# 3_Digital.net
KiCad netlist of a schematic drawn in Altium Designer
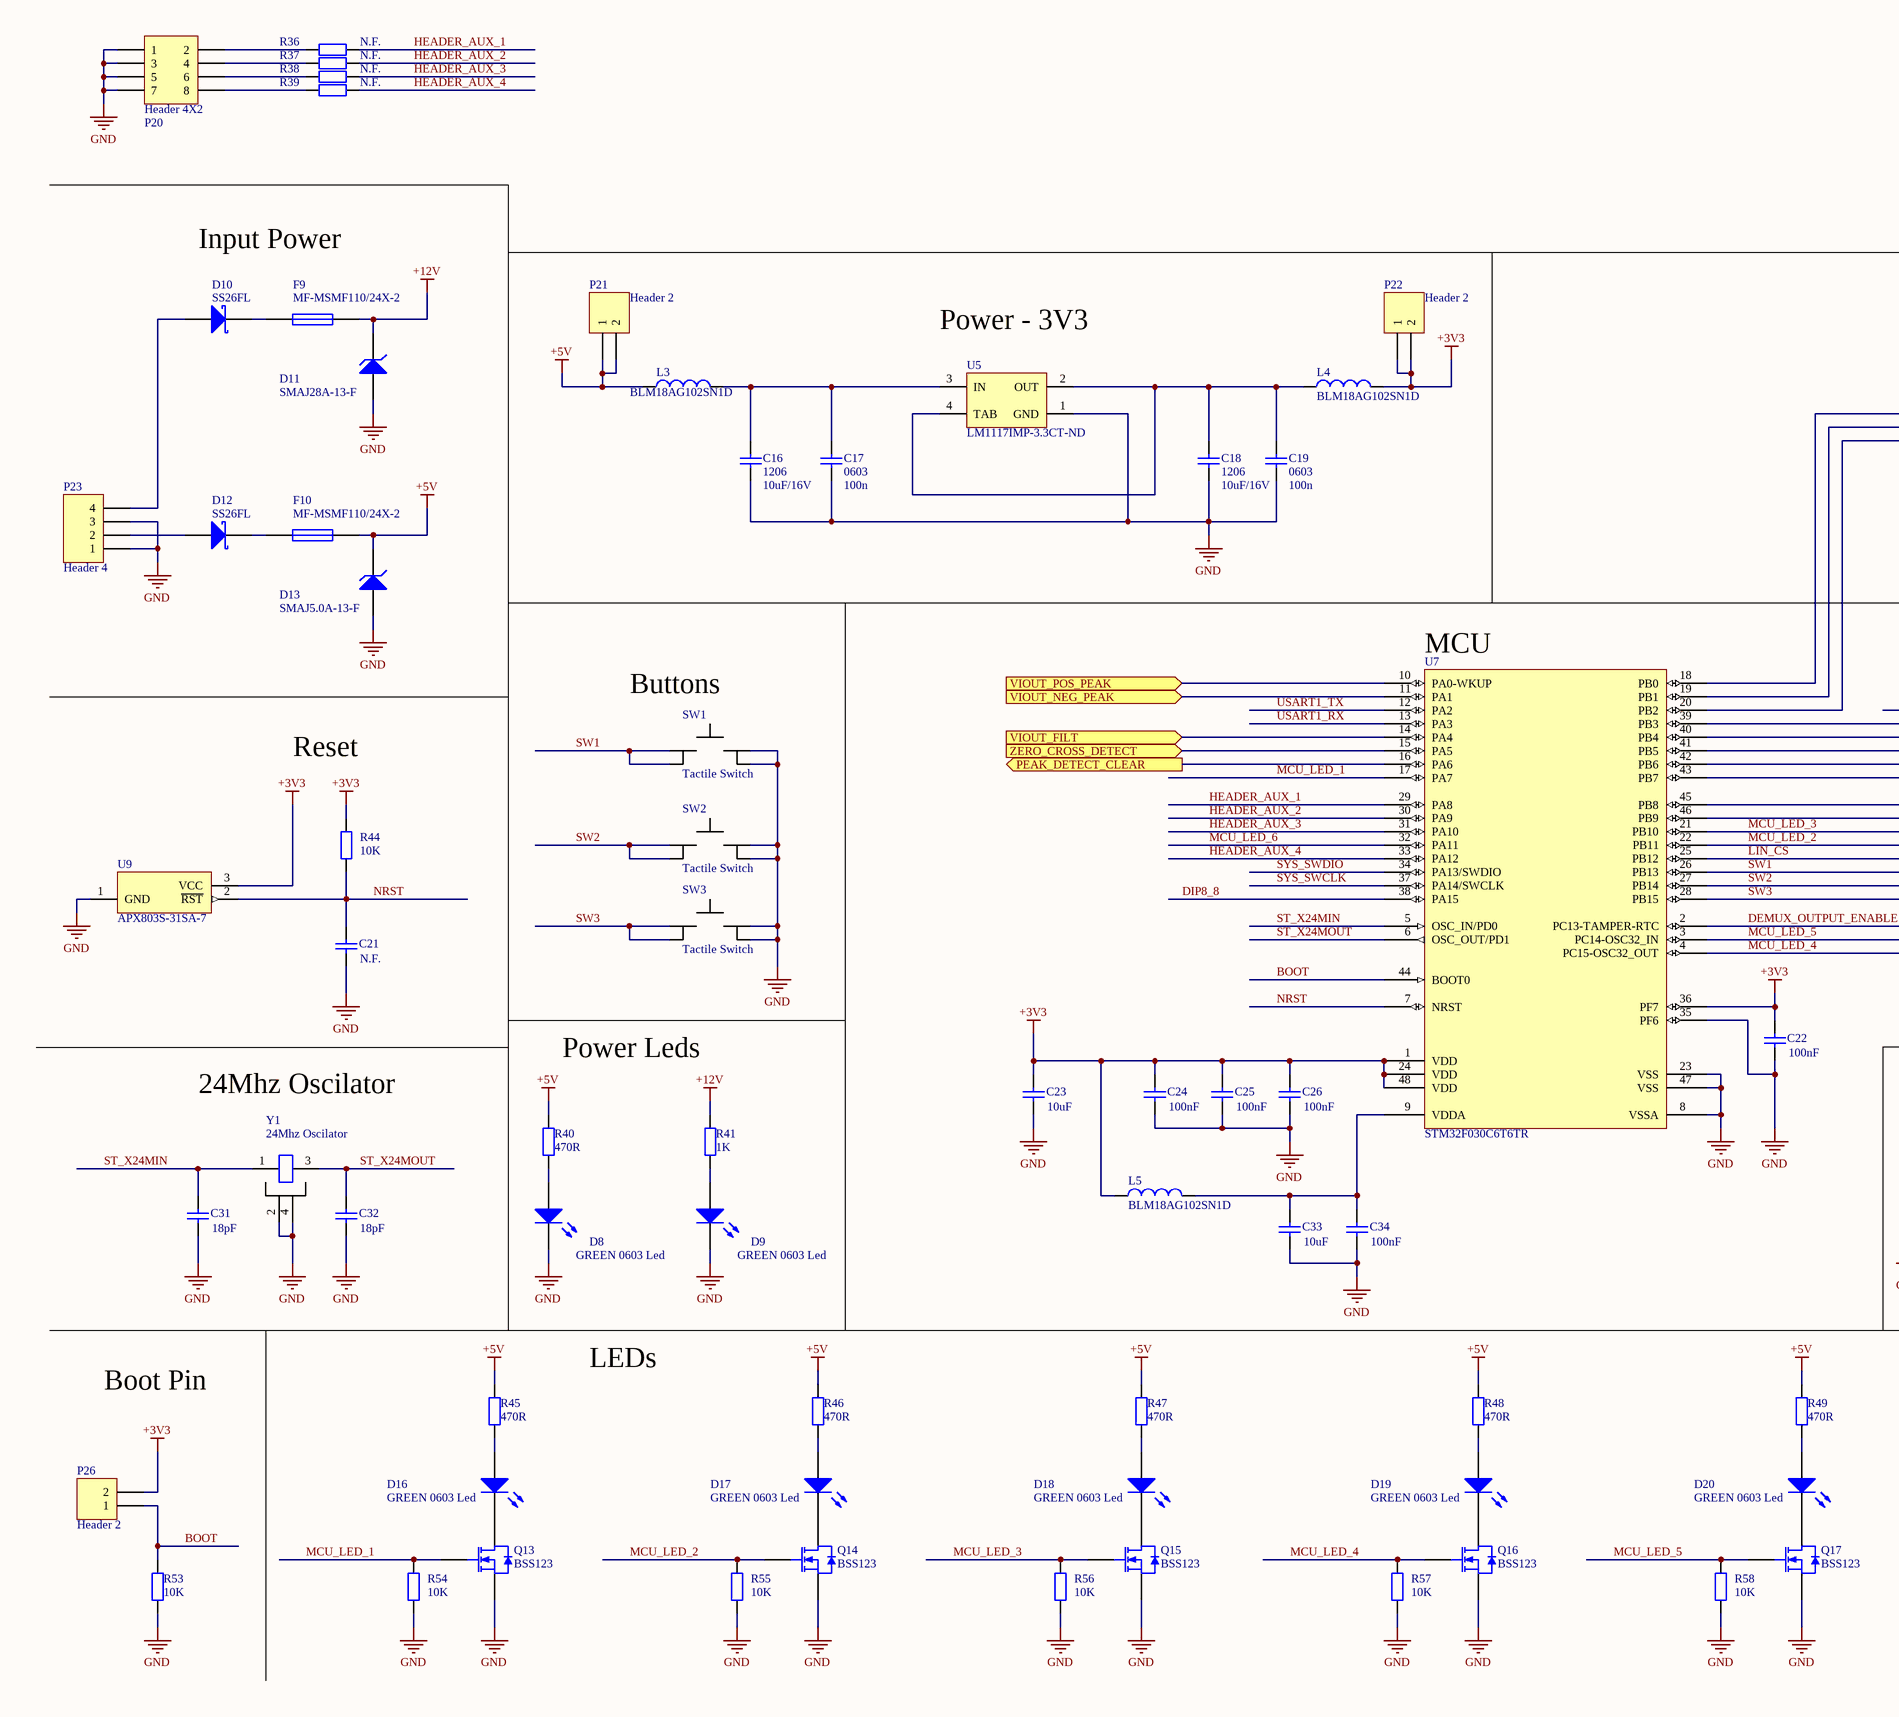
[diagram p0: [3]Digital.SchDoc, left]
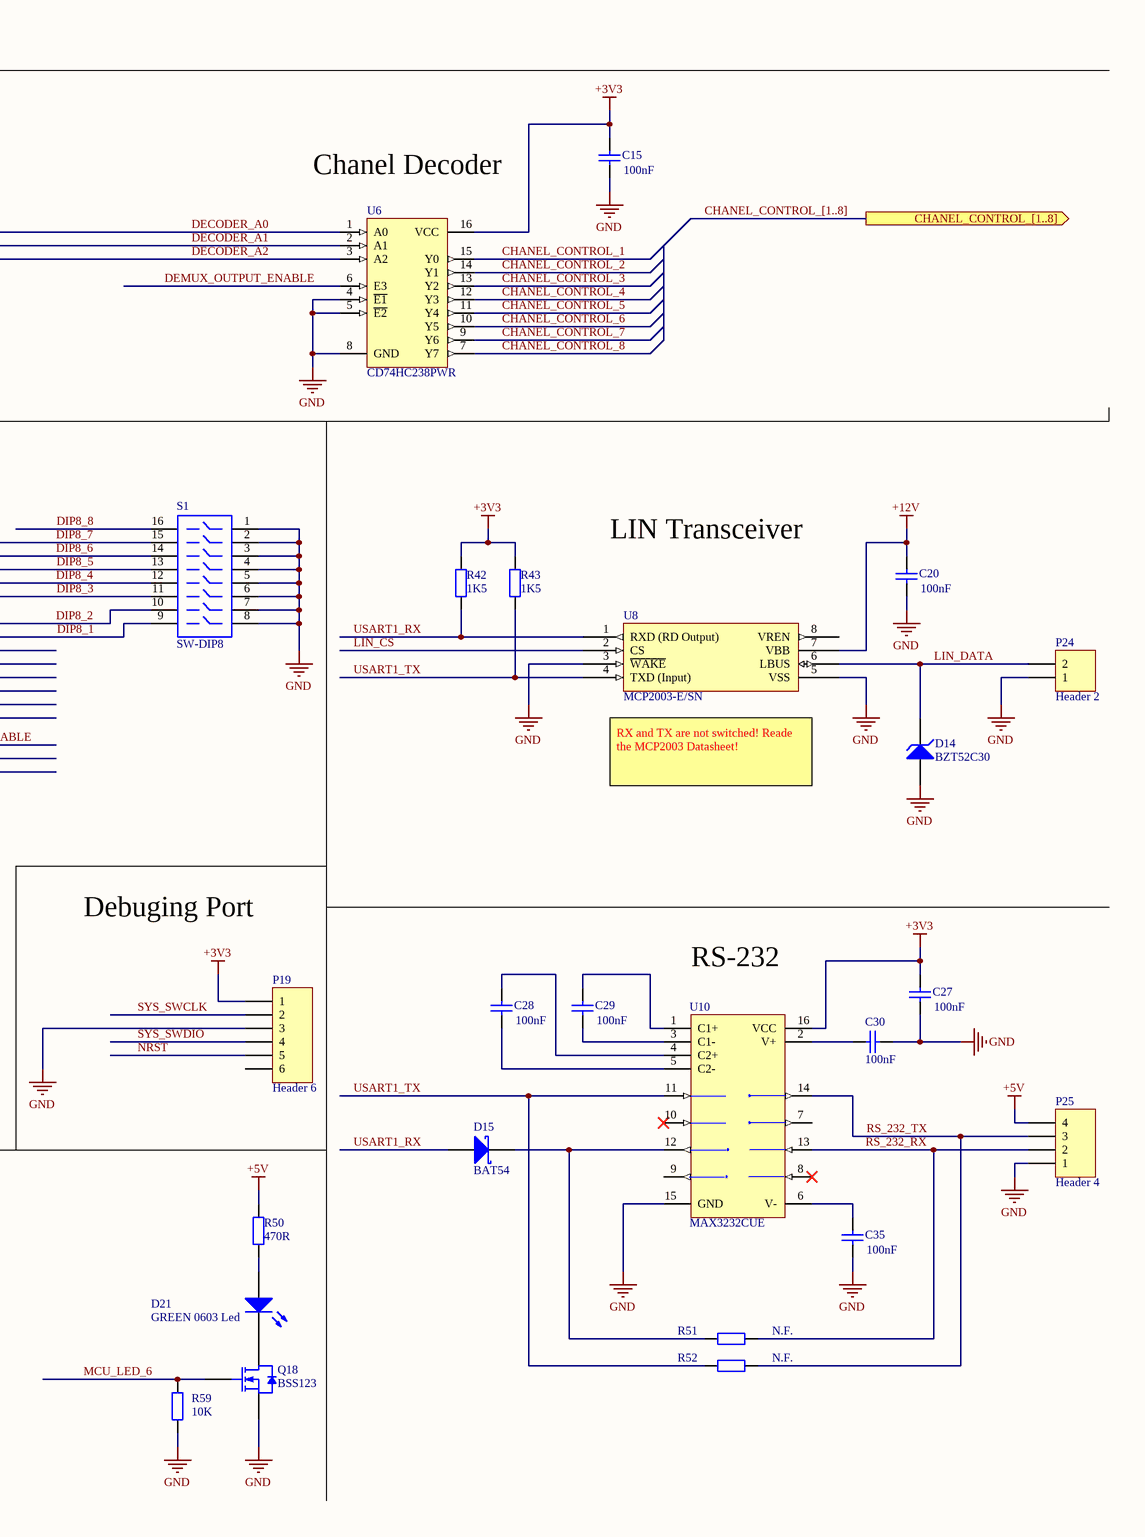
[diagram p1: [3]Digital.SchDoc, right]

(export (version "E")
  (design (tool "Eeschema 10.0.6"))
  (components
    (comp (ref "C15")
      (value "100nF")
      (footprint "1608[0603]")
      (description "Capacitor")
      (fields (field (name "Comment") "0603") (field (name "PUBLISHER") "Altium Limited"))
      (libsource (lib "Miscellaneous Devices") (part "Cap"))
    )
    (comp (ref "C16")
      (value "1206")
      (footprint "C1206")
      (description "Capacitor")
      (fields (field (name "ALTIUM_VALUE") "10uF/16V") (field (name "PUBLISHER") "Altium Limited"))
      (libsource (lib "Miscellaneous Devices") (part "Cap"))
    )
    (comp (ref "C17")
      (value "0603")
      (footprint "1608[0603]")
      (description "Capacitor")
      (fields (field (name "ALTIUM_VALUE") "100n") (field (name "PUBLISHER") "Altium Limited"))
      (libsource (lib "Miscellaneous Devices") (part "Cap"))
    )
    (comp (ref "C18")
      (value "1206")
      (footprint "C1206")
      (description "Capacitor")
      (fields (field (name "ALTIUM_VALUE") "10uF/16V") (field (name "PUBLISHER") "Altium Limited"))
      (libsource (lib "Miscellaneous Devices") (part "Cap"))
    )
    (comp (ref "C19")
      (value "0603")
      (footprint "1608[0603]")
      (description "Capacitor")
      (fields (field (name "ALTIUM_VALUE") "100n") (field (name "PUBLISHER") "Altium Limited"))
      (libsource (lib "Miscellaneous Devices") (part "Cap"))
    )
    (comp (ref "C20")
      (value "100nF")
      (footprint "1608[0603]")
      (description "Capacitor")
      (fields (field (name "Comment") "0603") (field (name "PUBLISHER") "Altium Limited"))
      (libsource (lib "Miscellaneous Devices") (part "Cap"))
    )
    (comp (ref "C21")
      (value "N.F.")
      (footprint "1608[0603]")
      (description "Capacitor")
      (fields (field (name "Comment") "0603") (field (name "PUBLISHER") "Altium Limited"))
      (libsource (lib "Miscellaneous Devices") (part "Cap"))
    )
    (comp (ref "C22")
      (value "100nF")
      (footprint "1608[0603]")
      (description "Capacitor")
      (fields (field (name "Comment") "0603") (field (name "PUBLISHER") "Altium Limited"))
      (libsource (lib "Miscellaneous Devices") (part "Cap"))
    )
    (comp (ref "C23")
      (value "10uF")
      (footprint "1608[0603]")
      (description "Capacitor")
      (fields (field (name "Comment") "0603") (field (name "PUBLISHER") "Altium Limited"))
      (libsource (lib "Miscellaneous Devices") (part "Cap"))
    )
    (comp (ref "C24")
      (value "100nF")
      (footprint "1608[0603]")
      (description "Capacitor")
      (fields (field (name "Comment") "0603") (field (name "PUBLISHER") "Altium Limited"))
      (libsource (lib "Miscellaneous Devices") (part "Cap"))
    )
    (comp (ref "C25")
      (value "100nF")
      (footprint "1608[0603]")
      (description "Capacitor")
      (fields (field (name "Comment") "0603") (field (name "PUBLISHER") "Altium Limited"))
      (libsource (lib "Miscellaneous Devices") (part "Cap"))
    )
    (comp (ref "C26")
      (value "100nF")
      (footprint "1608[0603]")
      (description "Capacitor")
      (fields (field (name "Comment") "0603") (field (name "PUBLISHER") "Altium Limited"))
      (libsource (lib "Miscellaneous Devices") (part "Cap"))
    )
    (comp (ref "C27")
      (value "100nF")
      (footprint "1608[0603]")
      (description "Capacitor")
      (fields (field (name "Comment") "0603") (field (name "PUBLISHER") "Altium Limited"))
      (libsource (lib "Miscellaneous Devices") (part "Cap"))
    )
    (comp (ref "C28")
      (value "100nF")
      (footprint "1608[0603]")
      (description "Capacitor")
      (fields (field (name "Comment") "0603") (field (name "PUBLISHER") "Altium Limited"))
      (libsource (lib "Miscellaneous Devices") (part "Cap"))
    )
    (comp (ref "C29")
      (value "100nF")
      (footprint "1608[0603]")
      (description "Capacitor")
      (fields (field (name "Comment") "0603") (field (name "PUBLISHER") "Altium Limited"))
      (libsource (lib "Miscellaneous Devices") (part "Cap"))
    )
    (comp (ref "C30")
      (value "100nF")
      (footprint "1608[0603]")
      (description "Capacitor")
      (fields (field (name "Comment") "0603") (field (name "PUBLISHER") "Altium Limited"))
      (libsource (lib "Miscellaneous Devices") (part "Cap"))
    )
    (comp (ref "C31")
      (value "18pF")
      (footprint "1608[0603]")
      (description "Capacitor")
      (fields (field (name "Comment") "0603") (field (name "PUBLISHER") "Altium Limited"))
      (libsource (lib "Miscellaneous Devices") (part "Cap"))
    )
    (comp (ref "C32")
      (value "18pF")
      (footprint "1608[0603]")
      (description "Capacitor")
      (fields (field (name "Comment") "0603") (field (name "PUBLISHER") "Altium Limited"))
      (libsource (lib "Miscellaneous Devices") (part "Cap"))
    )
    (comp (ref "C33")
      (value "10uF")
      (footprint "1608[0603]")
      (description "Capacitor")
      (fields (field (name "Comment") "0603") (field (name "PUBLISHER") "Altium Limited"))
      (libsource (lib "Miscellaneous Devices") (part "Cap"))
    )
    (comp (ref "C34")
      (value "100nF")
      (footprint "1608[0603]")
      (description "Capacitor")
      (fields (field (name "Comment") "0603") (field (name "PUBLISHER") "Altium Limited"))
      (libsource (lib "Miscellaneous Devices") (part "Cap"))
    )
    (comp (ref "C35")
      (value "100nF")
      (footprint "1608[0603]")
      (description "Capacitor")
      (fields (field (name "Comment") "0603") (field (name "PUBLISHER") "Altium Limited"))
      (libsource (lib "Miscellaneous Devices") (part "Cap"))
    )
    (comp (ref "D8")
      (value "GREEN 0603 Led")
      (footprint "LED0603")
      (description "Typical INFRARED GaAs LED")
      (fields
        (field (name "MANUFACTURER PART NO.") "KPT-1608CGCK")
        (field (name "PUBLISHER") "Altium Limited")
      )
      (libsource (lib "Miscellaneous Devices") (part "LED0"))
    )
    (comp (ref "D9")
      (value "GREEN 0603 Led")
      (footprint "LED0603")
      (description "Typical INFRARED GaAs LED")
      (fields
        (field (name "MANUFACTURER PART NO.") "KPT-1608CGCK")
        (field (name "PUBLISHER") "Altium Limited")
      )
      (libsource (lib "Miscellaneous Devices") (part "LED0"))
    )
    (comp (ref "D10")
      (value "SS26FL")
      (footprint "SOD123F")
      (description "Schottky Rectifier")
      (fields (field (name "PUBLISHER") "Altium Limited"))
      (libsource (lib "Miscellaneous Devices") (part "Diode 11DQ03"))
    )
    (comp (ref "D11")
      (value "SMAJ28A-13-F")
      (footprint "SMA")
      (description "Zener Diode")
      (fields (field (name "PUBLISHER") "Altium Limited"))
      (libsource (lib "Miscellaneous Devices") (part "D Zener"))
    )
    (comp (ref "D12")
      (value "SS26FL")
      (footprint "SOD123F")
      (description "Schottky Rectifier")
      (fields (field (name "PUBLISHER") "Altium Limited"))
      (libsource (lib "Miscellaneous Devices") (part "Diode 11DQ03"))
    )
    (comp (ref "D13")
      (value "SMAJ5.0A-13-F")
      (footprint "SMA")
      (description "Zener Diode")
      (fields (field (name "PUBLISHER") "Altium Limited"))
      (libsource (lib "Miscellaneous Devices") (part "D Zener"))
    )
    (comp (ref "D14")
      (value "BZT52C30")
      (footprint "SOD123")
      (description "Zener Diode")
      (fields
        (field (name "MANUFACTURER PART NO.") "BZT52C30-7-F")
        (field (name "PUBLISHER") "Altium Limited")
      )
      (libsource (lib "Miscellaneous Devices") (part "D Zener"))
    )
    (comp (ref "D15")
      (value "BAT54")
      (footprint "SOT-23_N")
      (description "Silicon RF Schottky Diode for Mixer Applications in the VHF/UHF Range")
      (fields (field (name "MANUFACTURER PART NO.") "BAT54LT1G") (field (name "PUBLISHER") "Altium Limited"))
      (libsource (lib "Miscellaneous Devices") (part "Diode BAT17"))
    )
    (comp (ref "D16")
      (value "GREEN 0603 Led")
      (footprint "LED0603")
      (description "Typical INFRARED GaAs LED")
      (fields
        (field (name "MANUFACTURER PART NO.") "KPT-1608CGCK")
        (field (name "PUBLISHER") "Altium Limited")
      )
      (libsource (lib "Miscellaneous Devices") (part "LED0"))
    )
    (comp (ref "D17")
      (value "GREEN 0603 Led")
      (footprint "LED0603")
      (description "Typical INFRARED GaAs LED")
      (fields
        (field (name "MANUFACTURER PART NO.") "KPT-1608CGCK")
        (field (name "PUBLISHER") "Altium Limited")
      )
      (libsource (lib "Miscellaneous Devices") (part "LED0"))
    )
    (comp (ref "D18")
      (value "GREEN 0603 Led")
      (footprint "LED0603")
      (description "Typical INFRARED GaAs LED")
      (fields
        (field (name "MANUFACTURER PART NO.") "KPT-1608CGCK")
        (field (name "PUBLISHER") "Altium Limited")
      )
      (libsource (lib "Miscellaneous Devices") (part "LED0"))
    )
    (comp (ref "D19")
      (value "GREEN 0603 Led")
      (footprint "LED0603")
      (description "Typical INFRARED GaAs LED")
      (fields
        (field (name "MANUFACTURER PART NO.") "KPT-1608CGCK")
        (field (name "PUBLISHER") "Altium Limited")
      )
      (libsource (lib "Miscellaneous Devices") (part "LED0"))
    )
    (comp (ref "D20")
      (value "GREEN 0603 Led")
      (footprint "LED0603")
      (description "Typical INFRARED GaAs LED")
      (fields
        (field (name "MANUFACTURER PART NO.") "KPT-1608CGCK")
        (field (name "PUBLISHER") "Altium Limited")
      )
      (libsource (lib "Miscellaneous Devices") (part "LED0"))
    )
    (comp (ref "D21")
      (value "GREEN 0603 Led")
      (footprint "LED0603")
      (description "Typical INFRARED GaAs LED")
      (fields
        (field (name "MANUFACTURER PART NO.") "KPT-1608CGCK")
        (field (name "PUBLISHER") "Altium Limited")
      )
      (libsource (lib "Miscellaneous Devices") (part "LED0"))
    )
    (comp (ref "F9")
      (value "MF-MSMF110/24X-2")
      (footprint "CAPC4532L")
      (description "Fuse")
      (fields
        (field (name "MANUFACTURER PART NO.") "MF-MSMF050-2")
        (field (name "PUBLISHER") "Altium Limited")
      )
      (libsource (lib "Miscellaneous Devices") (part "Fuse 1"))
    )
    (comp (ref "F10")
      (value "MF-MSMF110/24X-2")
      (footprint "CAPC4532L")
      (description "Fuse")
      (fields
        (field (name "MANUFACTURER PART NO.") "MF-MSMF050-2")
        (field (name "PUBLISHER") "Altium Limited")
      )
      (libsource (lib "Miscellaneous Devices") (part "Fuse 1"))
    )
    (comp (ref "L3")
      (value "BLM18AG102SN1D")
      (footprint "1608[0603]")
      (description "Inductor")
      (libsource (lib "Miscellaneous Devices") (part "Inductor"))
    )
    (comp (ref "L4")
      (value "BLM18AG102SN1D")
      (footprint "1608[0603]")
      (description "Inductor")
      (libsource (lib "Miscellaneous Devices") (part "Inductor"))
    )
    (comp (ref "L5")
      (value "BLM18AG102SN1D")
      (footprint "1608[0603]")
      (description "Inductor")
      (libsource (lib "Miscellaneous Devices") (part "Inductor"))
    )
    (comp (ref "P19")
      (value "Header 6")
      (footprint "HDR1X6")
      (description "Header, 6-Pin")
      (fields (field (name "PUBLISHER") "Altium Limited"))
      (libsource (lib "Miscellaneous Connectors") (part "Header 6"))
    )
    (comp (ref "P20")
      (value "Header 4X2")
      (footprint "HDR2X4")
      (description "Header, 4-Pin, Dual row")
      (fields (field (name "PUBLISHER") "Altium Limited"))
      (libsource (lib "Miscellaneous Connectors") (part "Header 4X2"))
    )
    (comp (ref "P21")
      (value "Header 2")
      (footprint "HDR1X2")
      (description "Header, 2-Pin")
      (fields (field (name "PUBLISHER") "Altium Limited"))
      (libsource (lib "Miscellaneous Connectors") (part "Header 2"))
    )
    (comp (ref "P22")
      (value "Header 2")
      (footprint "HDR1X2")
      (description "Header, 2-Pin")
      (fields (field (name "PUBLISHER") "Altium Limited"))
      (libsource (lib "Miscellaneous Connectors") (part "Header 2"))
    )
    (comp (ref "P23")
      (value "Header 4")
      (footprint "284391-4")
      (description "Header, 4-Pin")
      (fields (field (name "PUBLISHER") "Altium Limited"))
      (libsource (lib "Miscellaneous Connectors") (part "Header 4"))
    )
    (comp (ref "P24")
      (value "Header 2")
      (footprint "284391-2")
      (description "Header, 2-Pin")
      (fields (field (name "PUBLISHER") "Altium Limited"))
      (libsource (lib "Miscellaneous Connectors") (part "Header 2"))
    )
    (comp (ref "P25")
      (value "Header 4")
      (footprint "284391-4")
      (description "Header, 4-Pin")
      (fields (field (name "PUBLISHER") "Altium Limited"))
      (libsource (lib "") (part "Header 4_1"))
    )
    (comp (ref "P26")
      (value "Header 2")
      (footprint "HDR1X2")
      (description "Header, 2-Pin")
      (fields (field (name "PUBLISHER") "Altium Limited"))
      (libsource (lib "") (part "Header 2_1"))
    )
    (comp (ref "Q13")
      (value "BSS123")
      (footprint "SOT23_N")
      (description "N-channel Enhancement Mode Vertical D-MOSFET")
      (fields (field (name "PUBLISHER") "Altium Limited"))
      (libsource (lib "Philips Discrete MOSFET - Low Power") (part "BSS123"))
    )
    (comp (ref "Q14")
      (value "BSS123")
      (footprint "SOT23_N")
      (description "N-channel Enhancement Mode Vertical D-MOSFET")
      (fields (field (name "PUBLISHER") "Altium Limited"))
      (libsource (lib "Philips Discrete MOSFET - Low Power") (part "BSS123"))
    )
    (comp (ref "Q15")
      (value "BSS123")
      (footprint "SOT23_N")
      (description "N-channel Enhancement Mode Vertical D-MOSFET")
      (fields (field (name "PUBLISHER") "Altium Limited"))
      (libsource (lib "Philips Discrete MOSFET - Low Power") (part "BSS123"))
    )
    (comp (ref "Q16")
      (value "BSS123")
      (footprint "SOT23_N")
      (description "N-channel Enhancement Mode Vertical D-MOSFET")
      (fields (field (name "PUBLISHER") "Altium Limited"))
      (libsource (lib "Philips Discrete MOSFET - Low Power") (part "BSS123"))
    )
    (comp (ref "Q17")
      (value "BSS123")
      (footprint "SOT23_N")
      (description "N-channel Enhancement Mode Vertical D-MOSFET")
      (fields (field (name "PUBLISHER") "Altium Limited"))
      (libsource (lib "Philips Discrete MOSFET - Low Power") (part "BSS123"))
    )
    (comp (ref "Q18")
      (value "BSS123")
      (footprint "SOT23_N")
      (description "N-channel Enhancement Mode Vertical D-MOSFET")
      (fields (field (name "PUBLISHER") "Altium Limited"))
      (libsource (lib "Philips Discrete MOSFET - Low Power") (part "BSS123"))
    )
    (comp (ref "R36")
      (value "N.F.")
      (footprint "J1-0603")
      (description "Resistor")
      (fields (field (name "Comment") "0603") (field (name "PUBLISHER") "Altium Limited"))
      (libsource (lib "Miscellaneous Devices") (part "Res2"))
    )
    (comp (ref "R37")
      (value "N.F.")
      (footprint "J1-0603")
      (description "Resistor")
      (fields (field (name "Comment") "0603") (field (name "PUBLISHER") "Altium Limited"))
      (libsource (lib "Miscellaneous Devices") (part "Res2"))
    )
    (comp (ref "R38")
      (value "N.F.")
      (footprint "J1-0603")
      (description "Resistor")
      (fields (field (name "Comment") "0603") (field (name "PUBLISHER") "Altium Limited"))
      (libsource (lib "Miscellaneous Devices") (part "Res2"))
    )
    (comp (ref "R39")
      (value "N.F.")
      (footprint "J1-0603")
      (description "Resistor")
      (fields (field (name "Comment") "0603") (field (name "PUBLISHER") "Altium Limited"))
      (libsource (lib "Miscellaneous Devices") (part "Res2"))
    )
    (comp (ref "R40")
      (value "470R")
      (footprint "J1-0603")
      (description "Resistor")
      (fields (field (name "Comment") "0603") (field (name "PUBLISHER") "Altium Limited"))
      (libsource (lib "") (part "Res2_1"))
    )
    (comp (ref "R41")
      (value "1K")
      (footprint "J1-0603")
      (description "Resistor")
      (fields (field (name "Comment") "0603") (field (name "PUBLISHER") "Altium Limited"))
      (libsource (lib "") (part "Res2_1"))
    )
    (comp (ref "R42")
      (value "1K5")
      (footprint "J1-0603")
      (description "Resistor")
      (fields (field (name "Comment") "0603") (field (name "PUBLISHER") "Altium Limited"))
      (libsource (lib "") (part "Res2_1"))
    )
    (comp (ref "R43")
      (value "1K5")
      (footprint "J1-0603")
      (description "Resistor")
      (fields (field (name "Comment") "0603") (field (name "PUBLISHER") "Altium Limited"))
      (libsource (lib "") (part "Res2_1"))
    )
    (comp (ref "R44")
      (value "10K")
      (footprint "J1-0603")
      (description "Resistor")
      (fields (field (name "Comment") "0603") (field (name "PUBLISHER") "Altium Limited"))
      (libsource (lib "") (part "Res2_1"))
    )
    (comp (ref "R45")
      (value "470R")
      (footprint "J1-0603")
      (description "Resistor")
      (fields (field (name "Comment") "0603") (field (name "PUBLISHER") "Altium Limited"))
      (libsource (lib "") (part "Res2_1"))
    )
    (comp (ref "R46")
      (value "470R")
      (footprint "J1-0603")
      (description "Resistor")
      (fields (field (name "Comment") "0603") (field (name "PUBLISHER") "Altium Limited"))
      (libsource (lib "") (part "Res2_1"))
    )
    (comp (ref "R47")
      (value "470R")
      (footprint "J1-0603")
      (description "Resistor")
      (fields (field (name "Comment") "0603") (field (name "PUBLISHER") "Altium Limited"))
      (libsource (lib "") (part "Res2_1"))
    )
    (comp (ref "R48")
      (value "470R")
      (footprint "J1-0603")
      (description "Resistor")
      (fields (field (name "Comment") "0603") (field (name "PUBLISHER") "Altium Limited"))
      (libsource (lib "") (part "Res2_1"))
    )
    (comp (ref "R49")
      (value "470R")
      (footprint "J1-0603")
      (description "Resistor")
      (fields (field (name "Comment") "0603") (field (name "PUBLISHER") "Altium Limited"))
      (libsource (lib "") (part "Res2_1"))
    )
    (comp (ref "R50")
      (value "470R")
      (footprint "J1-0603")
      (description "Resistor")
      (fields (field (name "Comment") "0603") (field (name "PUBLISHER") "Altium Limited"))
      (libsource (lib "") (part "Res2_1"))
    )
    (comp (ref "R51")
      (value "N.F.")
      (footprint "J1-0603")
      (description "Resistor")
      (fields (field (name "Comment") "0603") (field (name "PUBLISHER") "Altium Limited"))
      (libsource (lib "") (part "Res2_2"))
    )
    (comp (ref "R52")
      (value "N.F.")
      (footprint "J1-0603")
      (description "Resistor")
      (fields (field (name "Comment") "0603") (field (name "PUBLISHER") "Altium Limited"))
      (libsource (lib "") (part "Res2_2"))
    )
    (comp (ref "R53")
      (value "10K")
      (footprint "J1-0603")
      (description "Resistor")
      (fields (field (name "Comment") "0603") (field (name "PUBLISHER") "Altium Limited"))
      (libsource (lib "") (part "Res2_3"))
    )
    (comp (ref "R54")
      (value "10K")
      (footprint "J1-0603")
      (description "Resistor")
      (fields (field (name "Comment") "0603") (field (name "PUBLISHER") "Altium Limited"))
      (libsource (lib "") (part "Res2_1"))
    )
    (comp (ref "R55")
      (value "10K")
      (footprint "J1-0603")
      (description "Resistor")
      (fields (field (name "Comment") "0603") (field (name "PUBLISHER") "Altium Limited"))
      (libsource (lib "") (part "Res2_1"))
    )
    (comp (ref "R56")
      (value "10K")
      (footprint "J1-0603")
      (description "Resistor")
      (fields (field (name "Comment") "0603") (field (name "PUBLISHER") "Altium Limited"))
      (libsource (lib "") (part "Res2_1"))
    )
    (comp (ref "R57")
      (value "10K")
      (footprint "J1-0603")
      (description "Resistor")
      (fields (field (name "Comment") "0603") (field (name "PUBLISHER") "Altium Limited"))
      (libsource (lib "") (part "Res2_1"))
    )
    (comp (ref "R58")
      (value "10K")
      (footprint "J1-0603")
      (description "Resistor")
      (fields (field (name "Comment") "0603") (field (name "PUBLISHER") "Altium Limited"))
      (libsource (lib "") (part "Res2_1"))
    )
    (comp (ref "R59")
      (value "10K")
      (footprint "J1-0603")
      (description "Resistor")
      (fields (field (name "Comment") "0603") (field (name "PUBLISHER") "Altium Limited"))
      (libsource (lib "") (part "Res2_1"))
    )
    (comp (ref "S1")
      (value "SW-DIP8")
      (footprint "DIP-16-KEY")
      (description "4009 Series DIP Switch, Raised actuator")
      (fields (field (name "MANUFACTURER PART NO.") "210-8MS") (field (name "PUBLISHER") "Altium Limited"))
      (libsource (lib "Miscellaneous Devices") (part "SW-DIP8"))
    )
    (comp (ref "SW1")
      (value "Tactile Switch")
      (footprint "FSM14JLH")
      (fields (field (name "MANUFACTURER PART NO.") "FSM4JH"))
      (libsource (lib "VPay_1.0") (part "Tactile Switch"))
    )
    (comp (ref "SW2")
      (value "Tactile Switch")
      (footprint "FSM14JLH")
      (fields (field (name "MANUFACTURER PART NO.") "FSM4JH"))
      (libsource (lib "VPay_1.0") (part "Tactile Switch"))
    )
    (comp (ref "SW3")
      (value "Tactile Switch")
      (footprint "FSM14JLH")
      (fields (field (name "MANUFACTURER PART NO.") "FSM4JH"))
      (libsource (lib "VPay_1.0") (part "Tactile Switch"))
    )
    (comp (ref "U5")
      (value "LM1117IMP-3.3CT-ND")
      (footprint "MP04A_N")
      (description "800mA Low-Dropout Linear Regulator")
      (fields
        (field (name "PARTNUMBER") "LM1117IMP-3.3")
        (field (name "MANUFACTURER") "National Semiconductor")
        (field (name "PUBLISHER") "Altium Limited")
      )
      (libsource (lib "OrbitCrypto_V2") (part "LM1117IMP-3.3"))
    )
    (comp (ref "U6")
      (value "CD74HC238PWR")
      (footprint "TSOP65P640-16AL")
      (description "High-Speed CMOS Logic 3- to 8-Line Decoder/Demultiplexer Inverting")
      (libsource (lib "ROV_Voltage_Switch") (part "CD74HC238PWR"))
    )
    (comp (ref "U7")
      (value "STM32F030C6T6TR")
      (footprint "LQFP48_N")
      (description "STM32 ARM-based 32-bit MCU with 32 Kbytes Flash, 48-pin LQFP, Industrial Temperature")
      (fields (field (name "PUBLISHER") "Altium Limited"))
      (libsource (lib "ST Microcontroller 32-Bit STM32") (part "STM32F030x4/6/8"))
    )
    (comp (ref "U8")
      (value "MCP2003-E/SN")
      (footprint "SOIC127P600-8AL")
      (description "LIN J2602 Transceiver")
      (libsource (lib "ROV_Voltage_Switch") (part "MCP2003"))
    )
    (comp (ref "U9")
      (value "APX803S-31SA-7")
      (footprint "RT-3")
      (description "Microprocessor Supervisory Circuit in 3-Pin SOT-23")
      (fields (field (name "PUBLISHER") "Altium Limited"))
      (libsource (lib "AD Power Mgt Supervisory Circuit") (part "ADM809TART"))
    )
    (comp (ref "U10")
      (value "MAX3232CUE")
      (footprint "TSSOP16_L")
      (description "3.0V TO 5.5V, Low-Power, up to 1Mbps, True RS-232 Transceiver Using Four 0.1µF External Capacitor")
      (fields
        (field (name "MANUFACTURER PART NO.") "MAX3232EIPWRQ1")
        (field (name "PUBLISHER") "Altium Limited")
      )
      (libsource (lib "Maxim Communication Transceiver") (part "MAX3232CUE"))
    )
    (comp (ref "Y1")
      (value "24Mhz Oscilator")
      (footprint "SMD Crysta 2 x 1.6")
      (fields (field (name "MANUFACTURER PART NO.") "XRCGB24M000F2P00R0"))
      (libsource (lib "VPay_1.0") (part "XTAL"))
    )
  )
  (nets
    (net (code "1") (name "+3V3") (class "Default")
      (node (ref "C15") (pin "2") (pinfunction "2_2") (pintype "passive"))
      (node (ref "C22") (pin "2") (pinfunction "2_2") (pintype "passive"))
      (node (ref "C23") (pin "2") (pinfunction "2_2") (pintype "passive"))
      (node (ref "C24") (pin "2") (pinfunction "2_2") (pintype "passive"))
      (node (ref "C25") (pin "2") (pinfunction "2_2") (pintype "passive"))
      (node (ref "C26") (pin "2") (pinfunction "2_2") (pintype "passive"))
      (node (ref "C27") (pin "2") (pinfunction "2_2") (pintype "passive"))
      (node (ref "L4") (pin "2") (pinfunction "2_2") (pintype "passive"))
      (node (ref "L5") (pin "1") (pinfunction "1_1") (pintype "passive"))
      (node (ref "P19") (pin "1") (pinfunction "1_1") (pintype "passive"))
      (node (ref "P22") (pin "1") (pinfunction "1_1") (pintype "passive"))
      (node (ref "P22") (pin "2") (pinfunction "2_2") (pintype "passive"))
      (node (ref "P26") (pin "2") (pinfunction "2_2") (pintype "passive"))
      (node (ref "R42") (pin "2") (pinfunction "2_2") (pintype "passive"))
      (node (ref "R43") (pin "2") (pinfunction "2_2") (pintype "passive"))
      (node (ref "R44") (pin "2") (pinfunction "2_2") (pintype "passive"))
      (node (ref "U10") (pin "16") (pinfunction "VCC_16") (pintype "power_in"))
      (node (ref "U6") (pin "16") (pinfunction "VCC_16") (pintype "power_in"))
      (node (ref "U7") (pin "1") (pinfunction "VDD_1") (pintype "power_in"))
      (node (ref "U7") (pin "24") (pinfunction "VDD_24") (pintype "power_in"))
      (node (ref "U7") (pin "36") (pinfunction "PF7_36") (pintype "bidirectional"))
      (node (ref "U7") (pin "48") (pinfunction "VDD_48") (pintype "power_in"))
      (node (ref "U9") (pin "3") (pinfunction "VCC_3") (pintype "power_in"))
    )
    (net (code "2") (name "+5V") (class "Default")
      (node (ref "D13") (pin "2") (pinfunction "K_2") (pintype "passive"))
      (node (ref "F10") (pin "2") (pinfunction "2_2") (pintype "passive"))
      (node (ref "L3") (pin "1") (pinfunction "1_1") (pintype "passive"))
      (node (ref "P21") (pin "1") (pinfunction "1_1") (pintype "passive"))
      (node (ref "P21") (pin "2") (pinfunction "2_2") (pintype "passive"))
      (node (ref "P25") (pin "4") (pinfunction "4_4") (pintype "passive"))
      (node (ref "R40") (pin "2") (pinfunction "2_2") (pintype "passive"))
      (node (ref "R45") (pin "2") (pinfunction "2_2") (pintype "passive"))
      (node (ref "R46") (pin "2") (pinfunction "2_2") (pintype "passive"))
      (node (ref "R47") (pin "2") (pinfunction "2_2") (pintype "passive"))
      (node (ref "R48") (pin "2") (pinfunction "2_2") (pintype "passive"))
      (node (ref "R49") (pin "2") (pinfunction "2_2") (pintype "passive"))
      (node (ref "R50") (pin "2") (pinfunction "2_2") (pintype "passive"))
    )
    (net (code "3") (name "+12V") (class "Default")
      (node (ref "C20") (pin "2") (pinfunction "2_2") (pintype "passive"))
      (node (ref "D11") (pin "2") (pinfunction "K_2") (pintype "passive"))
      (node (ref "F9") (pin "2") (pinfunction "2_2") (pintype "passive"))
      (node (ref "R41") (pin "2") (pinfunction "2_2") (pintype "passive"))
      (node (ref "U8") (pin "7") (pinfunction "VBB_7") (pintype "power_in"))
    )
    (net (code "4") (name "/BOOT") (class "Default")
      (node (ref "P26") (pin "1") (pinfunction "1_1") (pintype "passive"))
      (node (ref "R53") (pin "1") (pinfunction "1_1") (pintype "passive"))
      (node (ref "U7") (pin "44") (pinfunction "BOOT0_44") (pintype "input"))
    )
    (net (code "5") (name "/CHANEL_CONTROL_1") (class "Default")
      (node (ref "U6") (pin "15") (pinfunction "Y0_15") (pintype "output"))
    )
    (net (code "6") (name "/CHANEL_CONTROL_2") (class "Default")
      (node (ref "U6") (pin "14") (pinfunction "Y1_14") (pintype "output"))
    )
    (net (code "7") (name "/CHANEL_CONTROL_3") (class "Default")
      (node (ref "U6") (pin "13") (pinfunction "Y2_13") (pintype "output"))
    )
    (net (code "8") (name "/CHANEL_CONTROL_4") (class "Default")
      (node (ref "U6") (pin "12") (pinfunction "Y3_12") (pintype "output"))
    )
    (net (code "9") (name "/CHANEL_CONTROL_5") (class "Default")
      (node (ref "U6") (pin "11") (pinfunction "Y4_11") (pintype "output"))
    )
    (net (code "10") (name "/CHANEL_CONTROL_6") (class "Default")
      (node (ref "U6") (pin "10") (pinfunction "Y5_10") (pintype "output"))
    )
    (net (code "11") (name "/CHANEL_CONTROL_7") (class "Default")
      (node (ref "U6") (pin "9") (pinfunction "Y6_9") (pintype "output"))
    )
    (net (code "12") (name "/CHANEL_CONTROL_8") (class "Default")
      (node (ref "U6") (pin "7") (pinfunction "Y7_7") (pintype "output"))
    )
    (net (code "14") (name "/DECODER_A0") (class "Default")
      (node (ref "U6") (pin "1") (pinfunction "A0_1") (pintype "input"))
      (node (ref "U7") (pin "18") (pinfunction "PB0_18") (pintype "bidirectional"))
    )
    (net (code "15") (name "/DECODER_A1") (class "Default")
      (node (ref "U6") (pin "2") (pinfunction "A1_2") (pintype "input"))
      (node (ref "U7") (pin "19") (pinfunction "PB1_19") (pintype "bidirectional"))
    )
    (net (code "16") (name "/DECODER_A2") (class "Default")
      (node (ref "U6") (pin "3") (pinfunction "A2_3") (pintype "input"))
      (node (ref "U7") (pin "20") (pinfunction "PB2_20") (pintype "bidirectional"))
    )
    (net (code "17") (name "/DEMUX_OUTPUT_ENABLE") (class "Default")
      (node (ref "U6") (pin "6") (pinfunction "E3_6") (pintype "input"))
      (node (ref "U7") (pin "2") (pinfunction "PC13-TAMPER-RTC_2") (pintype "bidirectional"))
    )
    (net (code "18") (name "/DIP8_1") (class "Default")
      (node (ref "S1") (pin "9") (pinfunction "9_9") (pintype "passive"))
      (node (ref "U7") (pin "46") (pinfunction "PB9_46") (pintype "bidirectional"))
    )
    (net (code "19") (name "/DIP8_2") (class "Default")
      (node (ref "S1") (pin "10") (pinfunction "10_10") (pintype "passive"))
      (node (ref "U7") (pin "45") (pinfunction "PB8_45") (pintype "bidirectional"))
    )
    (net (code "20") (name "/DIP8_3") (class "Default")
      (node (ref "S1") (pin "11") (pinfunction "11_11") (pintype "passive"))
      (node (ref "U7") (pin "43") (pinfunction "PB7_43") (pintype "bidirectional"))
    )
    (net (code "21") (name "/DIP8_4") (class "Default")
      (node (ref "S1") (pin "12") (pinfunction "12_12") (pintype "passive"))
      (node (ref "U7") (pin "42") (pinfunction "PB6_42") (pintype "bidirectional"))
    )
    (net (code "22") (name "/DIP8_5") (class "Default")
      (node (ref "S1") (pin "13") (pinfunction "13_13") (pintype "passive"))
      (node (ref "U7") (pin "41") (pinfunction "PB5_41") (pintype "bidirectional"))
    )
    (net (code "23") (name "/DIP8_6") (class "Default")
      (node (ref "S1") (pin "14") (pinfunction "14_14") (pintype "passive"))
      (node (ref "U7") (pin "40") (pinfunction "PB4_40") (pintype "bidirectional"))
    )
    (net (code "24") (name "/DIP8_7") (class "Default")
      (node (ref "S1") (pin "15") (pinfunction "15_15") (pintype "passive"))
      (node (ref "U7") (pin "39") (pinfunction "PB3_39") (pintype "bidirectional"))
    )
    (net (code "25") (name "/DIP8_8") (class "Default")
      (node (ref "S1") (pin "16") (pinfunction "16_16") (pintype "passive"))
      (node (ref "U7") (pin "38") (pinfunction "PA15_38") (pintype "bidirectional"))
    )
    (net (code "26") (name "/HEADER_AUX_1") (class "Default")
      (node (ref "R36") (pin "1") (pinfunction "1_1") (pintype "passive"))
      (node (ref "U7") (pin "29") (pinfunction "PA8_29") (pintype "bidirectional"))
    )
    (net (code "27") (name "/HEADER_AUX_2") (class "Default")
      (node (ref "R37") (pin "1") (pinfunction "1_1") (pintype "passive"))
      (node (ref "U7") (pin "30") (pinfunction "PA9_30") (pintype "bidirectional"))
    )
    (net (code "28") (name "/HEADER_AUX_3") (class "Default")
      (node (ref "R38") (pin "1") (pinfunction "1_1") (pintype "passive"))
      (node (ref "U7") (pin "31") (pinfunction "PA10_31") (pintype "bidirectional"))
    )
    (net (code "29") (name "/HEADER_AUX_4") (class "Default")
      (node (ref "R39") (pin "1") (pinfunction "1_1") (pintype "passive"))
      (node (ref "U7") (pin "33") (pinfunction "PA12_33") (pintype "bidirectional"))
    )
    (net (code "30") (name "/LIN_CS") (class "Default")
      (node (ref "U7") (pin "25") (pinfunction "PB12_25") (pintype "bidirectional"))
      (node (ref "U8") (pin "2") (pinfunction "CS_2") (pintype "input"))
    )
    (net (code "31") (name "/LIN_DATA") (class "Default")
      (node (ref "D14") (pin "2") (pinfunction "K_2") (pintype "passive"))
      (node (ref "P24") (pin "2") (pinfunction "2_2") (pintype "passive"))
      (node (ref "U8") (pin "6") (pinfunction "LBUS_6") (pintype "bidirectional"))
    )
    (net (code "32") (name "/MCU_LED_1") (class "Default")
      (node (ref "Q13") (pin "1") (pinfunction "G_1") (pintype "passive"))
      (node (ref "R54") (pin "2") (pinfunction "2_2") (pintype "passive"))
      (node (ref "U7") (pin "17") (pinfunction "PA7_17") (pintype "bidirectional"))
    )
    (net (code "33") (name "/MCU_LED_2") (class "Default")
      (node (ref "Q14") (pin "1") (pinfunction "G_1") (pintype "passive"))
      (node (ref "R55") (pin "2") (pinfunction "2_2") (pintype "passive"))
      (node (ref "U7") (pin "22") (pinfunction "PB11_22") (pintype "bidirectional"))
    )
    (net (code "34") (name "/MCU_LED_3") (class "Default")
      (node (ref "Q15") (pin "1") (pinfunction "G_1") (pintype "passive"))
      (node (ref "R56") (pin "2") (pinfunction "2_2") (pintype "passive"))
      (node (ref "U7") (pin "21") (pinfunction "PB10_21") (pintype "bidirectional"))
    )
    (net (code "35") (name "/MCU_LED_4") (class "Default")
      (node (ref "Q16") (pin "1") (pinfunction "G_1") (pintype "passive"))
      (node (ref "R57") (pin "2") (pinfunction "2_2") (pintype "passive"))
      (node (ref "U7") (pin "4") (pinfunction "PC15-OSC32_OUT_4") (pintype "bidirectional"))
    )
    (net (code "36") (name "/MCU_LED_5") (class "Default")
      (node (ref "Q17") (pin "1") (pinfunction "G_1") (pintype "passive"))
      (node (ref "R58") (pin "2") (pinfunction "2_2") (pintype "passive"))
      (node (ref "U7") (pin "3") (pinfunction "PC14-OSC32_IN_3") (pintype "bidirectional"))
    )
    (net (code "37") (name "/MCU_LED_6") (class "Default")
      (node (ref "Q18") (pin "1") (pinfunction "G_1") (pintype "passive"))
      (node (ref "R59") (pin "2") (pinfunction "2_2") (pintype "passive"))
      (node (ref "U7") (pin "32") (pinfunction "PA11_32") (pintype "bidirectional"))
    )
    (net (code "38") (name "/NRST") (class "Default")
      (node (ref "C21") (pin "2") (pinfunction "2_2") (pintype "passive"))
      (node (ref "P19") (pin "5") (pinfunction "5_5") (pintype "passive"))
      (node (ref "R44") (pin "1") (pinfunction "1_1") (pintype "passive"))
      (node (ref "U7") (pin "7") (pinfunction "NRST_7") (pintype "bidirectional"))
      (node (ref "U9") (pin "2") (pinfunction "~{RST}_2") (pintype "output"))
    )
    (net (code "39") (name "/PEAK_DETECT_CLEAR") (class "Default")
      (node (ref "U7") (pin "16") (pinfunction "PA6_16") (pintype "bidirectional"))
    )
    (net (code "40") (name "/RS_232_RX") (class "Default")
      (node (ref "P25") (pin "2") (pinfunction "2_2") (pintype "passive"))
      (node (ref "R51") (pin "2") (pinfunction "2_2") (pintype "passive"))
      (node (ref "U10") (pin "13") (pinfunction "R1IN_13") (pintype "input"))
    )
    (net (code "41") (name "/RS_232_TX") (class "Default")
      (node (ref "P25") (pin "3") (pinfunction "3_3") (pintype "passive"))
      (node (ref "R52") (pin "2") (pinfunction "2_2") (pintype "passive"))
      (node (ref "U10") (pin "14") (pinfunction "T1OUT_14") (pintype "output"))
    )
    (net (code "42") (name "/ST_X24MIN") (class "Default")
      (node (ref "C31") (pin "1") (pinfunction "1_1") (pintype "passive"))
      (node (ref "U7") (pin "5") (pinfunction "OSC_IN/PD0_5") (pintype "input"))
      (node (ref "Y1") (pin "1") (pinfunction "OSC1_1") (pintype "passive"))
    )
    (net (code "43") (name "/ST_X24MOUT") (class "Default")
      (node (ref "C32") (pin "1") (pinfunction "1_1") (pintype "passive"))
      (node (ref "U7") (pin "6") (pinfunction "OSC_OUT/PD1_6") (pintype "output"))
      (node (ref "Y1") (pin "3") (pinfunction "OSC2_3") (pintype "passive"))
    )
    (net (code "44") (name "/SW1") (class "Default")
      (node (ref "SW1") (pin "3") (pintype "passive"))
      (node (ref "SW1") (pin "4") (pintype "passive"))
      (node (ref "U7") (pin "26") (pinfunction "PB13_26") (pintype "bidirectional"))
    )
    (net (code "45") (name "/SW2") (class "Default")
      (node (ref "SW2") (pin "3") (pintype "passive"))
      (node (ref "SW2") (pin "4") (pintype "passive"))
      (node (ref "U7") (pin "27") (pinfunction "PB14_27") (pintype "bidirectional"))
    )
    (net (code "46") (name "/SW3") (class "Default")
      (node (ref "SW3") (pin "3") (pintype "passive"))
      (node (ref "SW3") (pin "4") (pintype "passive"))
      (node (ref "U7") (pin "28") (pinfunction "PB15_28") (pintype "bidirectional"))
    )
    (net (code "47") (name "/SYS_SWCLK") (class "Default")
      (node (ref "P19") (pin "2") (pinfunction "2_2") (pintype "passive"))
      (node (ref "U7") (pin "37") (pinfunction "PA14/SWCLK_37") (pintype "bidirectional"))
    )
    (net (code "48") (name "/SYS_SWDIO") (class "Default")
      (node (ref "P19") (pin "4") (pinfunction "4_4") (pintype "passive"))
      (node (ref "U7") (pin "34") (pinfunction "PA13/SWDIO_34") (pintype "bidirectional"))
    )
    (net (code "49") (name "/USART1_RX") (class "Default")
      (node (ref "D15") (pin "1") (pinfunction "A_1") (pintype "passive"))
      (node (ref "R42") (pin "1") (pinfunction "1_1") (pintype "passive"))
      (node (ref "U7") (pin "13") (pinfunction "PA3_13") (pintype "bidirectional"))
      (node (ref "U8") (pin "1") (pinfunction "RXD_(RD_Output)_1") (pintype "output"))
    )
    (net (code "50") (name "/USART1_TX") (class "Default")
      (node (ref "R43") (pin "1") (pinfunction "1_1") (pintype "passive"))
      (node (ref "R52") (pin "1") (pinfunction "1_1") (pintype "passive"))
      (node (ref "U10") (pin "11") (pinfunction "T1IN_11") (pintype "input"))
      (node (ref "U7") (pin "12") (pinfunction "PA2_12") (pintype "bidirectional"))
      (node (ref "U8") (pin "4") (pinfunction "TXD_(Input)_4") (pintype "input"))
    )
    (net (code "51") (name "/VIOUT_FILT") (class "Default")
      (node (ref "U7") (pin "14") (pinfunction "PA4_14") (pintype "bidirectional"))
    )
    (net (code "52") (name "/VIOUT_NEG_PEAK") (class "Default")
      (node (ref "U7") (pin "11") (pinfunction "PA1_11") (pintype "bidirectional"))
    )
    (net (code "53") (name "/VIOUT_POS_PEAK") (class "Default")
      (node (ref "U7") (pin "10") (pinfunction "PA0-WKUP_10") (pintype "bidirectional"))
    )
    (net (code "54") (name "/ZERO_CROSS_DETECT") (class "Default")
      (node (ref "U7") (pin "15") (pinfunction "PA5_15") (pintype "bidirectional"))
    )
    (net (code "55") (name "GND") (class "Default")
      (node (ref "C15") (pin "1") (pinfunction "1_1") (pintype "passive"))
      (node (ref "C16") (pin "1") (pinfunction "1_1") (pintype "passive"))
      (node (ref "C17") (pin "1") (pinfunction "1_1") (pintype "passive"))
      (node (ref "C18") (pin "1") (pinfunction "1_1") (pintype "passive"))
      (node (ref "C19") (pin "1") (pinfunction "1_1") (pintype "passive"))
      (node (ref "C20") (pin "1") (pinfunction "1_1") (pintype "passive"))
      (node (ref "C21") (pin "1") (pinfunction "1_1") (pintype "passive"))
      (node (ref "C22") (pin "1") (pinfunction "1_1") (pintype "passive"))
      (node (ref "C23") (pin "1") (pinfunction "1_1") (pintype "passive"))
      (node (ref "C24") (pin "1") (pinfunction "1_1") (pintype "passive"))
      (node (ref "C25") (pin "1") (pinfunction "1_1") (pintype "passive"))
      (node (ref "C26") (pin "1") (pinfunction "1_1") (pintype "passive"))
      (node (ref "C27") (pin "1") (pinfunction "1_1") (pintype "passive"))
      (node (ref "C30") (pin "1") (pinfunction "1_1") (pintype "passive"))
      (node (ref "C31") (pin "2") (pinfunction "2_2") (pintype "passive"))
      (node (ref "C32") (pin "2") (pinfunction "2_2") (pintype "passive"))
      (node (ref "C33") (pin "1") (pinfunction "1_1") (pintype "passive"))
      (node (ref "C34") (pin "1") (pinfunction "1_1") (pintype "passive"))
      (node (ref "C35") (pin "1") (pinfunction "1_1") (pintype "passive"))
      (node (ref "D11") (pin "1") (pinfunction "A_1") (pintype "passive"))
      (node (ref "D13") (pin "1") (pinfunction "A_1") (pintype "passive"))
      (node (ref "D14") (pin "1") (pinfunction "A_1") (pintype "passive"))
      (node (ref "D8") (pin "2") (pinfunction "K_2") (pintype "passive"))
      (node (ref "D9") (pin "2") (pinfunction "K_2") (pintype "passive"))
      (node (ref "P19") (pin "3") (pinfunction "3_3") (pintype "passive"))
      (node (ref "P20") (pin "1") (pinfunction "1_1") (pintype "passive"))
      (node (ref "P20") (pin "3") (pinfunction "3_3") (pintype "passive"))
      (node (ref "P20") (pin "5") (pinfunction "5_5") (pintype "passive"))
      (node (ref "P20") (pin "7") (pinfunction "7_7") (pintype "passive"))
      (node (ref "P23") (pin "1") (pinfunction "1_1") (pintype "passive"))
      (node (ref "P23") (pin "3") (pinfunction "3_3") (pintype "passive"))
      (node (ref "P24") (pin "1") (pinfunction "1_1") (pintype "passive"))
      (node (ref "P25") (pin "1") (pinfunction "1_1") (pintype "passive"))
      (node (ref "Q13") (pin "2") (pinfunction "S_2") (pintype "passive"))
      (node (ref "Q14") (pin "2") (pinfunction "S_2") (pintype "passive"))
      (node (ref "Q15") (pin "2") (pinfunction "S_2") (pintype "passive"))
      (node (ref "Q16") (pin "2") (pinfunction "S_2") (pintype "passive"))
      (node (ref "Q17") (pin "2") (pinfunction "S_2") (pintype "passive"))
      (node (ref "Q18") (pin "2") (pinfunction "S_2") (pintype "passive"))
      (node (ref "R53") (pin "2") (pinfunction "2_2") (pintype "passive"))
      (node (ref "R54") (pin "1") (pinfunction "1_1") (pintype "passive"))
      (node (ref "R55") (pin "1") (pinfunction "1_1") (pintype "passive"))
      (node (ref "R56") (pin "1") (pinfunction "1_1") (pintype "passive"))
      (node (ref "R57") (pin "1") (pinfunction "1_1") (pintype "passive"))
      (node (ref "R58") (pin "1") (pinfunction "1_1") (pintype "passive"))
      (node (ref "R59") (pin "1") (pinfunction "1_1") (pintype "passive"))
      (node (ref "S1") (pin "1") (pinfunction "1_1") (pintype "passive"))
      (node (ref "S1") (pin "2") (pinfunction "2_2") (pintype "passive"))
      (node (ref "S1") (pin "3") (pinfunction "3_3") (pintype "passive"))
      (node (ref "S1") (pin "4") (pinfunction "4_4") (pintype "passive"))
      (node (ref "S1") (pin "5") (pinfunction "5_5") (pintype "passive"))
      (node (ref "S1") (pin "6") (pinfunction "6_6") (pintype "passive"))
      (node (ref "S1") (pin "7") (pinfunction "7_7") (pintype "passive"))
      (node (ref "S1") (pin "8") (pinfunction "8_8") (pintype "passive"))
      (node (ref "SW1") (pin "1") (pintype "passive"))
      (node (ref "SW1") (pin "2") (pintype "passive"))
      (node (ref "SW2") (pin "1") (pintype "passive"))
      (node (ref "SW2") (pin "2") (pintype "passive"))
      (node (ref "SW3") (pin "1") (pintype "passive"))
      (node (ref "SW3") (pin "2") (pintype "passive"))
      (node (ref "U10") (pin "15") (pinfunction "GND_15") (pintype "power_in"))
      (node (ref "U5") (pin "1") (pinfunction "GND_1") (pintype "power_in"))
      (node (ref "U6") (pin "4") (pinfunction "~{E1}_4") (pintype "input"))
      (node (ref "U6") (pin "5") (pinfunction "~{E2}_5") (pintype "input"))
      (node (ref "U6") (pin "8") (pinfunction "GND_8") (pintype "power_in"))
      (node (ref "U7") (pin "23") (pinfunction "VSS_23") (pintype "power_in"))
      (node (ref "U7") (pin "35") (pinfunction "PF6_35") (pintype "bidirectional"))
      (node (ref "U7") (pin "47") (pinfunction "VSS_47") (pintype "power_in"))
      (node (ref "U7") (pin "8") (pinfunction "VSSA_8") (pintype "power_in"))
      (node (ref "U8") (pin "3") (pinfunction "~{WAKE}_3") (pintype "input"))
      (node (ref "U8") (pin "5") (pinfunction "VSS_5") (pintype "power_in"))
      (node (ref "U9") (pin "1") (pinfunction "GND_1") (pintype "power_in"))
      (node (ref "Y1") (pin "2") (pinfunction "GND_2") (pintype "passive"))
      (node (ref "Y1") (pin "4") (pinfunction "4_4") (pintype "passive"))
    )
    (net (code "56") (name "Net-(D8-A)") (class "Default")
      (node (ref "D8") (pin "1") (pinfunction "A_1") (pintype "passive"))
      (node (ref "R40") (pin "1") (pinfunction "1_1") (pintype "passive"))
    )
    (net (code "57") (name "Net-(D9-A)") (class "Default")
      (node (ref "D9") (pin "1") (pinfunction "A_1") (pintype "passive"))
      (node (ref "R41") (pin "1") (pinfunction "1_1") (pintype "passive"))
    )
    (net (code "58") (name "Net-(D10-A)") (class "Default")
      (node (ref "D10") (pin "1") (pinfunction "A_1") (pintype "passive"))
      (node (ref "P23") (pin "4") (pinfunction "4_4") (pintype "passive"))
    )
    (net (code "59") (name "Net-(D10-K)") (class "Default")
      (node (ref "D10") (pin "2") (pinfunction "K_2") (pintype "passive"))
      (node (ref "F9") (pin "1") (pinfunction "1_1") (pintype "passive"))
    )
    (net (code "60") (name "Net-(D12-A)") (class "Default")
      (node (ref "D12") (pin "1") (pinfunction "A_1") (pintype "passive"))
      (node (ref "P23") (pin "2") (pinfunction "2_2") (pintype "passive"))
    )
    (net (code "61") (name "Net-(D12-K)") (class "Default")
      (node (ref "D12") (pin "2") (pinfunction "K_2") (pintype "passive"))
      (node (ref "F10") (pin "1") (pinfunction "1_1") (pintype "passive"))
    )
    (net (code "62") (name "Net-(D15-K)") (class "Default")
      (node (ref "D15") (pin "3") (pinfunction "K_3") (pintype "passive"))
      (node (ref "R51") (pin "1") (pinfunction "1_1") (pintype "passive"))
      (node (ref "U10") (pin "12") (pinfunction "R1OUT_12") (pintype "output"))
    )
    (net (code "63") (name "Net-(D16-A)") (class "Default")
      (node (ref "D16") (pin "1") (pinfunction "A_1") (pintype "passive"))
      (node (ref "R45") (pin "1") (pinfunction "1_1") (pintype "passive"))
    )
    (net (code "64") (name "Net-(D16-K)") (class "Default")
      (node (ref "D16") (pin "2") (pinfunction "K_2") (pintype "passive"))
      (node (ref "Q13") (pin "3") (pinfunction "D_3") (pintype "passive"))
    )
    (net (code "65") (name "Net-(D17-A)") (class "Default")
      (node (ref "D17") (pin "1") (pinfunction "A_1") (pintype "passive"))
      (node (ref "R46") (pin "1") (pinfunction "1_1") (pintype "passive"))
    )
    (net (code "66") (name "Net-(D17-K)") (class "Default")
      (node (ref "D17") (pin "2") (pinfunction "K_2") (pintype "passive"))
      (node (ref "Q14") (pin "3") (pinfunction "D_3") (pintype "passive"))
    )
    (net (code "67") (name "Net-(D18-A)") (class "Default")
      (node (ref "D18") (pin "1") (pinfunction "A_1") (pintype "passive"))
      (node (ref "R47") (pin "1") (pinfunction "1_1") (pintype "passive"))
    )
    (net (code "68") (name "Net-(D18-K)") (class "Default")
      (node (ref "D18") (pin "2") (pinfunction "K_2") (pintype "passive"))
      (node (ref "Q15") (pin "3") (pinfunction "D_3") (pintype "passive"))
    )
    (net (code "69") (name "Net-(D19-A)") (class "Default")
      (node (ref "D19") (pin "1") (pinfunction "A_1") (pintype "passive"))
      (node (ref "R48") (pin "1") (pinfunction "1_1") (pintype "passive"))
    )
    (net (code "70") (name "Net-(D19-K)") (class "Default")
      (node (ref "D19") (pin "2") (pinfunction "K_2") (pintype "passive"))
      (node (ref "Q16") (pin "3") (pinfunction "D_3") (pintype "passive"))
    )
    (net (code "71") (name "Net-(D20-A)") (class "Default")
      (node (ref "D20") (pin "1") (pinfunction "A_1") (pintype "passive"))
      (node (ref "R49") (pin "1") (pinfunction "1_1") (pintype "passive"))
    )
    (net (code "72") (name "Net-(D20-K)") (class "Default")
      (node (ref "D20") (pin "2") (pinfunction "K_2") (pintype "passive"))
      (node (ref "Q17") (pin "3") (pinfunction "D_3") (pintype "passive"))
    )
    (net (code "73") (name "Net-(D21-A)") (class "Default")
      (node (ref "D21") (pin "1") (pinfunction "A_1") (pintype "passive"))
      (node (ref "R50") (pin "1") (pinfunction "1_1") (pintype "passive"))
    )
    (net (code "74") (name "Net-(D21-K)") (class "Default")
      (node (ref "D21") (pin "2") (pinfunction "K_2") (pintype "passive"))
      (node (ref "Q18") (pin "3") (pinfunction "D_3") (pintype "passive"))
    )
    (net (code "75") (name "Net-(P20-Pad2)") (class "Default")
      (node (ref "P20") (pin "2") (pinfunction "2_2") (pintype "passive"))
      (node (ref "R36") (pin "2") (pinfunction "2_2") (pintype "passive"))
    )
    (net (code "76") (name "Net-(P20-Pad4)") (class "Default")
      (node (ref "P20") (pin "4") (pinfunction "4_4") (pintype "passive"))
      (node (ref "R37") (pin "2") (pinfunction "2_2") (pintype "passive"))
    )
    (net (code "77") (name "Net-(P20-Pad6)") (class "Default")
      (node (ref "P20") (pin "6") (pinfunction "6_6") (pintype "passive"))
      (node (ref "R38") (pin "2") (pinfunction "2_2") (pintype "passive"))
    )
    (net (code "78") (name "Net-(P20-Pad8)") (class "Default")
      (node (ref "P20") (pin "8") (pinfunction "8_8") (pintype "passive"))
      (node (ref "R39") (pin "2") (pinfunction "2_2") (pintype "passive"))
    )
    (net (code "79") (name "Net-(U5-IN)") (class "Default")
      (node (ref "C16") (pin "2") (pinfunction "2_2") (pintype "passive"))
      (node (ref "C17") (pin "2") (pinfunction "2_2") (pintype "passive"))
      (node (ref "L3") (pin "2") (pinfunction "2_2") (pintype "passive"))
      (node (ref "U5") (pin "3") (pinfunction "IN_3") (pintype "power_in"))
    )
    (net (code "80") (name "Net-(U5-OUT)") (class "Default")
      (node (ref "C18") (pin "2") (pinfunction "2_2") (pintype "passive"))
      (node (ref "C19") (pin "2") (pinfunction "2_2") (pintype "passive"))
      (node (ref "L4") (pin "1") (pinfunction "1_1") (pintype "passive"))
      (node (ref "U5") (pin "2") (pinfunction "OUT_2") (pintype "power_in"))
      (node (ref "U5") (pin "4") (pinfunction "TAB_4") (pintype "power_in"))
    )
    (net (code "81") (name "Net-(U7-VDDA)") (class "Default")
      (node (ref "C33") (pin "2") (pinfunction "2_2") (pintype "passive"))
      (node (ref "C34") (pin "2") (pinfunction "2_2") (pintype "passive"))
      (node (ref "L5") (pin "2") (pinfunction "2_2") (pintype "passive"))
      (node (ref "U7") (pin "9") (pinfunction "VDDA_9") (pintype "power_in"))
    )
    (net (code "82") (name "Net-(U10-C1+)") (class "Default")
      (node (ref "C29") (pin "2") (pinfunction "2_2") (pintype "passive"))
      (node (ref "U10") (pin "1") (pinfunction "C1+_1") (pintype "passive"))
    )
    (net (code "83") (name "Net-(U10-C1-)") (class "Default")
      (node (ref "C29") (pin "1") (pinfunction "1_1") (pintype "passive"))
      (node (ref "U10") (pin "3") (pinfunction "C1-_3") (pintype "passive"))
    )
    (net (code "84") (name "Net-(U10-C2+)") (class "Default")
      (node (ref "C28") (pin "2") (pinfunction "2_2") (pintype "passive"))
      (node (ref "U10") (pin "4") (pinfunction "C2+_4") (pintype "passive"))
    )
    (net (code "85") (name "Net-(U10-C2-)") (class "Default")
      (node (ref "C28") (pin "1") (pinfunction "1_1") (pintype "passive"))
      (node (ref "U10") (pin "5") (pinfunction "C2-_5") (pintype "passive"))
    )
    (net (code "86") (name "Net-(U10-V+)") (class "Default")
      (node (ref "C30") (pin "2") (pinfunction "2_2") (pintype "passive"))
      (node (ref "U10") (pin "2") (pinfunction "V+_2") (pintype "power_in"))
    )
    (net (code "87") (name "Net-(U10-V-)") (class "Default")
      (node (ref "C35") (pin "2") (pinfunction "2_2") (pintype "passive"))
      (node (ref "U10") (pin "6") (pinfunction "V-_6") (pintype "power_in"))
    )
    (net (code "88") (name "unconnected-(P19-Pad6)") (class "Default")
      (node (ref "P19") (pin "6") (pinfunction "6_6") (pintype "passive"))
    )
    (net (code "89") (name "unconnected-(U8-VREN-Pad8)") (class "Default")
      (node (ref "U8") (pin "8") (pinfunction "VREN_8") (pintype "output"))
    )
    (net (code "90") (name "unconnected-(U10-R2IN-Pad8)") (class "Default")
      (node (ref "U10") (pin "8") (pinfunction "R2IN_8") (pintype "input+no_connect"))
    )
    (net (code "91") (name "unconnected-(U10-R2OUT-Pad9)") (class "Default")
      (node (ref "U10") (pin "9") (pinfunction "R2OUT_9") (pintype "output"))
    )
    (net (code "92") (name "unconnected-(U10-T2IN-Pad10)") (class "Default")
      (node (ref "U10") (pin "10") (pinfunction "T2IN_10") (pintype "input+no_connect"))
    )
    (net (code "93") (name "unconnected-(U10-T2OUT-Pad7)") (class "Default")
      (node (ref "U10") (pin "7") (pinfunction "T2OUT_7") (pintype "output"))
    )
  )
)
